# clock_generator.net
KiCad netlist of a schematic drawn in EAGLE
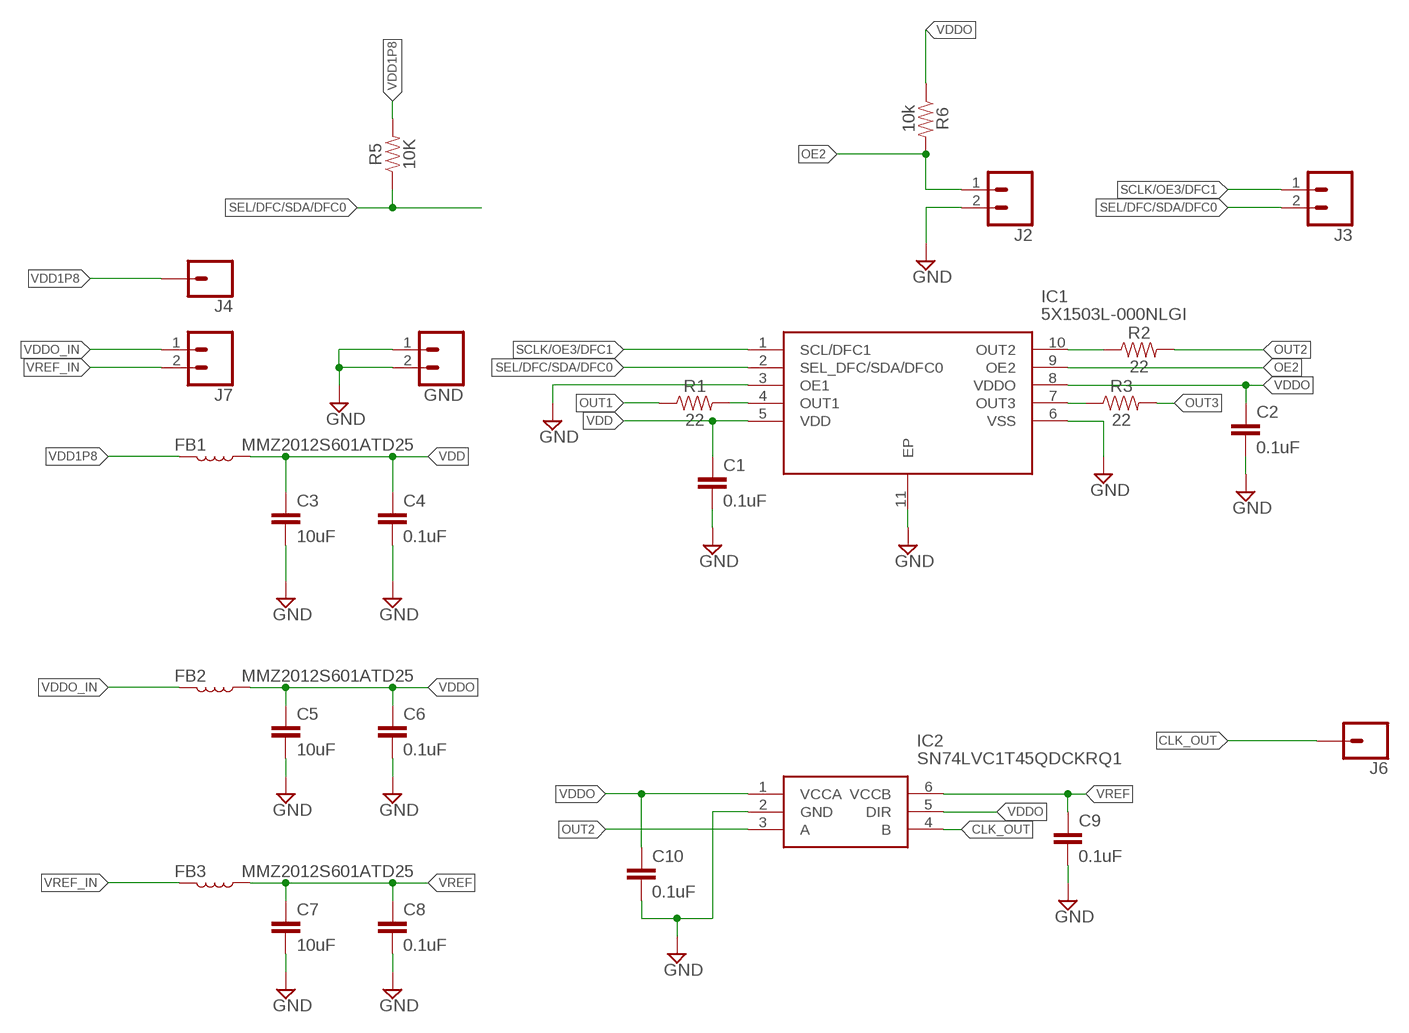
[diagram p0: schematic, sheet 1]

(export (version "E")
  (design (tool "Eeschema 10.0.6"))
  (components
    (comp (ref "C1")
      (value "0.1uF")
      (footprint "eagle-import:0805")
      (libsource (lib "eagle-import") (part "1.0UF-0805-25V-10%"))
    )
    (comp (ref "C2")
      (value "0.1uF")
      (footprint "eagle-import:0805")
      (libsource (lib "eagle-import") (part "1.0UF-0805-25V-10%"))
    )
    (comp (ref "C3")
      (value "10uF")
      (footprint "eagle-import:0805")
      (libsource (lib "eagle-import") (part "1.0UF-0805-25V-10%"))
    )
    (comp (ref "C4")
      (value "0.1uF")
      (footprint "eagle-import:0805")
      (libsource (lib "eagle-import") (part "1.0UF-0805-25V-10%"))
    )
    (comp (ref "C5")
      (value "10uF")
      (footprint "eagle-import:0805")
      (libsource (lib "eagle-import") (part "1.0UF-0805-25V-10%"))
    )
    (comp (ref "C6")
      (value "0.1uF")
      (footprint "eagle-import:0805")
      (libsource (lib "eagle-import") (part "1.0UF-0805-25V-10%"))
    )
    (comp (ref "C7")
      (value "10uF")
      (footprint "eagle-import:0805")
      (libsource (lib "eagle-import") (part "1.0UF-0805-25V-10%"))
    )
    (comp (ref "C8")
      (value "0.1uF")
      (footprint "eagle-import:0805")
      (libsource (lib "eagle-import") (part "1.0UF-0805-25V-10%"))
    )
    (comp (ref "C9")
      (value "0.1uF")
      (footprint "eagle-import:0805")
      (libsource (lib "eagle-import") (part "1.0UF-0805-25V-10%"))
    )
    (comp (ref "C10")
      (value "0.1uF")
      (footprint "eagle-import:0805")
      (libsource (lib "eagle-import") (part "1.0UF-0805-25V-10%"))
    )
    (comp (ref "FB1")
      (value "MMZ2012S601ATD25")
      (footprint "eagle-import:0805")
      (libsource (lib "eagle-import") (part "INDUCTOR-0805-3.3UH"))
    )
    (comp (ref "FB2")
      (value "MMZ2012S601ATD25")
      (footprint "eagle-import:0805")
      (libsource (lib "eagle-import") (part "INDUCTOR-0805-3.3UH"))
    )
    (comp (ref "FB3")
      (value "MMZ2012S601ATD25")
      (footprint "eagle-import:0805")
      (libsource (lib "eagle-import") (part "INDUCTOR-0805-3.3UH"))
    )
    (comp (ref "GND")
      (value "CONN_02")
      (footprint "eagle-import:1X02")
      (libsource (lib "eagle-import") (part "CONN_02"))
    )
    (comp (ref "IC1")
      (value "5X1503L-000NLGI")
      (footprint "eagle-import:SON40P200X200X110-11N")
      (fields (field (name "MOUSER_PART_NUMBER") "972-5X1503L-000NLGI"))
      (libsource (lib "eagle-import") (part "5X1503L-000NLGI"))
    )
    (comp (ref "IC2")
      (value "SN74LVC1T45QDCKRQ1")
      (footprint "eagle-import:SOT65P210X110-6N")
      (fields (field (name "MOUSER_PART_NUMBER") "595-74LVC1T45QDCKRQ1"))
      (libsource (lib "eagle-import") (part "SN74LVC1T45QDCKRQ1"))
    )
    (comp (ref "J2")
      (value "CONN_02")
      (footprint "eagle-import:1X02")
      (libsource (lib "eagle-import") (part "CONN_02"))
    )
    (comp (ref "J3")
      (value "CONN_02")
      (footprint "eagle-import:1X02")
      (libsource (lib "eagle-import") (part "CONN_02"))
    )
    (comp (ref "J4")
      (value "CONN_01")
      (footprint "eagle-import:1X01")
      (libsource (lib "eagle-import") (part "CONN_01"))
    )
    (comp (ref "J6")
      (value "CONN_01")
      (footprint "eagle-import:1X01")
      (libsource (lib "eagle-import") (part "CONN_01"))
    )
    (comp (ref "J7")
      (value "CONN_02")
      (footprint "eagle-import:1X02")
      (libsource (lib "eagle-import") (part "CONN_02"))
    )
    (comp (ref "R1")
      (value "22")
      (footprint "eagle-import:0805")
      (libsource (lib "eagle-import") (part "0.75OHM-0805-1/4W-1%"))
    )
    (comp (ref "R2")
      (value "22")
      (footprint "eagle-import:0805")
      (libsource (lib "eagle-import") (part "0.75OHM-0805-1/4W-1%"))
    )
    (comp (ref "R3")
      (value "22")
      (footprint "eagle-import:0805")
      (libsource (lib "eagle-import") (part "0.75OHM-0805-1/4W-1%"))
    )
    (comp (ref "R5")
      (value "10K")
      (footprint "eagle-import:0805")
      (libsource (lib "eagle-import") (part "0.75OHM-0805-1/4W-1%"))
    )
    (comp (ref "R6")
      (value "10k")
      (footprint "eagle-import:0805")
      (libsource (lib "eagle-import") (part "0.3OHM-0805-1/8W-1%"))
    )
  )
  (nets
    (net (code "1") (name "CLK_OUT") (class "Default")
      (node (ref "IC2") (pin "4") (pinfunction "B_4") (pintype "bidirectional"))
      (node (ref "J6") (pin "1") (pinfunction "1_1") (pintype "passive"))
    )
    (net (code "2") (name "GND") (class "Default")
      (node (ref "C1") (pin "2") (pinfunction "2_2") (pintype "passive"))
      (node (ref "C10") (pin "2") (pinfunction "2_2") (pintype "passive"))
      (node (ref "C2") (pin "2") (pinfunction "2_2") (pintype "passive"))
      (node (ref "C3") (pin "2") (pinfunction "2_2") (pintype "passive"))
      (node (ref "C4") (pin "2") (pinfunction "2_2") (pintype "passive"))
      (node (ref "C5") (pin "2") (pinfunction "2_2") (pintype "passive"))
      (node (ref "C6") (pin "2") (pinfunction "2_2") (pintype "passive"))
      (node (ref "C7") (pin "2") (pinfunction "2_2") (pintype "passive"))
      (node (ref "C8") (pin "2") (pinfunction "2_2") (pintype "passive"))
      (node (ref "C9") (pin "2") (pinfunction "2_2") (pintype "passive"))
      (node (ref "GND") (pin "1") (pinfunction "1_1") (pintype "passive"))
      (node (ref "GND") (pin "2") (pinfunction "2_2") (pintype "passive"))
      (node (ref "IC1") (pin "11") (pinfunction "EP_11") (pintype "bidirectional"))
      (node (ref "IC1") (pin "3") (pinfunction "OE1_3") (pintype "bidirectional"))
      (node (ref "IC1") (pin "6") (pinfunction "VSS_6") (pintype "bidirectional"))
      (node (ref "IC2") (pin "2") (pinfunction "GND_2") (pintype "bidirectional"))
      (node (ref "J2") (pin "2") (pinfunction "2_2") (pintype "passive"))
    )
    (net (code "3") (name "Net-(IC1-OUT1)") (class "Default")
      (node (ref "IC1") (pin "4") (pinfunction "OUT1_4") (pintype "bidirectional"))
      (node (ref "R1") (pin "2") (pinfunction "2_2") (pintype "passive"))
    )
    (net (code "4") (name "Net-(IC1-OUT2)") (class "Default")
      (node (ref "IC1") (pin "10") (pinfunction "OUT2_10") (pintype "bidirectional"))
      (node (ref "R2") (pin "1") (pinfunction "1_1") (pintype "passive"))
    )
    (net (code "5") (name "Net-(IC1-OUT3)") (class "Default")
      (node (ref "IC1") (pin "7") (pinfunction "OUT3_7") (pintype "bidirectional"))
      (node (ref "R3") (pin "1") (pinfunction "1_1") (pintype "passive"))
    )
    (net (code "6") (name "OE2") (class "Default")
      (node (ref "IC1") (pin "9") (pinfunction "OE2_9") (pintype "bidirectional"))
      (node (ref "J2") (pin "1") (pinfunction "1_1") (pintype "passive"))
      (node (ref "R6") (pin "2") (pinfunction "2_2") (pintype "passive"))
    )
    (net (code "7") (name "OUT1") (class "Default")
      (node (ref "R1") (pin "1") (pinfunction "1_1") (pintype "passive"))
    )
    (net (code "8") (name "OUT2") (class "Default")
      (node (ref "IC2") (pin "3") (pinfunction "A_3") (pintype "bidirectional"))
      (node (ref "R2") (pin "2") (pinfunction "2_2") (pintype "passive"))
    )
    (net (code "9") (name "OUT3") (class "Default")
      (node (ref "R3") (pin "2") (pinfunction "2_2") (pintype "passive"))
    )
    (net (code "10") (name "SCLK{slash}OE3{slash}DFC1") (class "Default")
      (node (ref "IC1") (pin "1") (pinfunction "SCL/DFC1_1") (pintype "bidirectional"))
      (node (ref "J3") (pin "1") (pinfunction "1_1") (pintype "passive"))
    )
    (net (code "11") (name "SEL{slash}DFC{slash}SDA{slash}DFC0") (class "Default")
      (node (ref "IC1") (pin "2") (pinfunction "SEL_DFC/SDA/DFC0_2") (pintype "bidirectional"))
      (node (ref "J3") (pin "2") (pinfunction "2_2") (pintype "passive"))
      (node (ref "R5") (pin "1") (pinfunction "1_1") (pintype "passive"))
    )
    (net (code "12") (name "VDD") (class "Default")
      (node (ref "C1") (pin "1") (pinfunction "1_1") (pintype "passive"))
      (node (ref "C3") (pin "1") (pinfunction "1_1") (pintype "passive"))
      (node (ref "C4") (pin "1") (pinfunction "1_1") (pintype "passive"))
      (node (ref "FB1") (pin "1") (pinfunction "1_1") (pintype "passive"))
      (node (ref "IC1") (pin "5") (pinfunction "VDD_5") (pintype "bidirectional"))
    )
    (net (code "13") (name "VDD1P8") (class "Default")
      (node (ref "FB1") (pin "2") (pinfunction "2_2") (pintype "passive"))
      (node (ref "J4") (pin "1") (pinfunction "1_1") (pintype "passive"))
      (node (ref "R5") (pin "2") (pinfunction "2_2") (pintype "passive"))
    )
    (net (code "14") (name "VDDO") (class "Default")
      (node (ref "C10") (pin "1") (pinfunction "1_1") (pintype "passive"))
      (node (ref "C2") (pin "1") (pinfunction "1_1") (pintype "passive"))
      (node (ref "C5") (pin "1") (pinfunction "1_1") (pintype "passive"))
      (node (ref "C6") (pin "1") (pinfunction "1_1") (pintype "passive"))
      (node (ref "FB2") (pin "1") (pinfunction "1_1") (pintype "passive"))
      (node (ref "IC1") (pin "8") (pinfunction "VDDO_8") (pintype "bidirectional"))
      (node (ref "IC2") (pin "1") (pinfunction "VCCA_1") (pintype "bidirectional"))
      (node (ref "IC2") (pin "5") (pinfunction "DIR_5") (pintype "bidirectional"))
      (node (ref "R6") (pin "1") (pinfunction "1_1") (pintype "passive"))
    )
    (net (code "15") (name "VDDO_IN") (class "Default")
      (node (ref "FB2") (pin "2") (pinfunction "2_2") (pintype "passive"))
      (node (ref "J7") (pin "1") (pinfunction "1_1") (pintype "passive"))
    )
    (net (code "16") (name "VREF") (class "Default")
      (node (ref "C7") (pin "1") (pinfunction "1_1") (pintype "passive"))
      (node (ref "C8") (pin "1") (pinfunction "1_1") (pintype "passive"))
      (node (ref "C9") (pin "1") (pinfunction "1_1") (pintype "passive"))
      (node (ref "FB3") (pin "1") (pinfunction "1_1") (pintype "passive"))
      (node (ref "IC2") (pin "6") (pinfunction "VCCB_6") (pintype "bidirectional"))
    )
    (net (code "17") (name "VREF_IN") (class "Default")
      (node (ref "FB3") (pin "2") (pinfunction "2_2") (pintype "passive"))
      (node (ref "J7") (pin "2") (pinfunction "2_2") (pintype "passive"))
    )
  )
)
